# BF24.net
KiCad netlist of a schematic drawn in Altium Designer
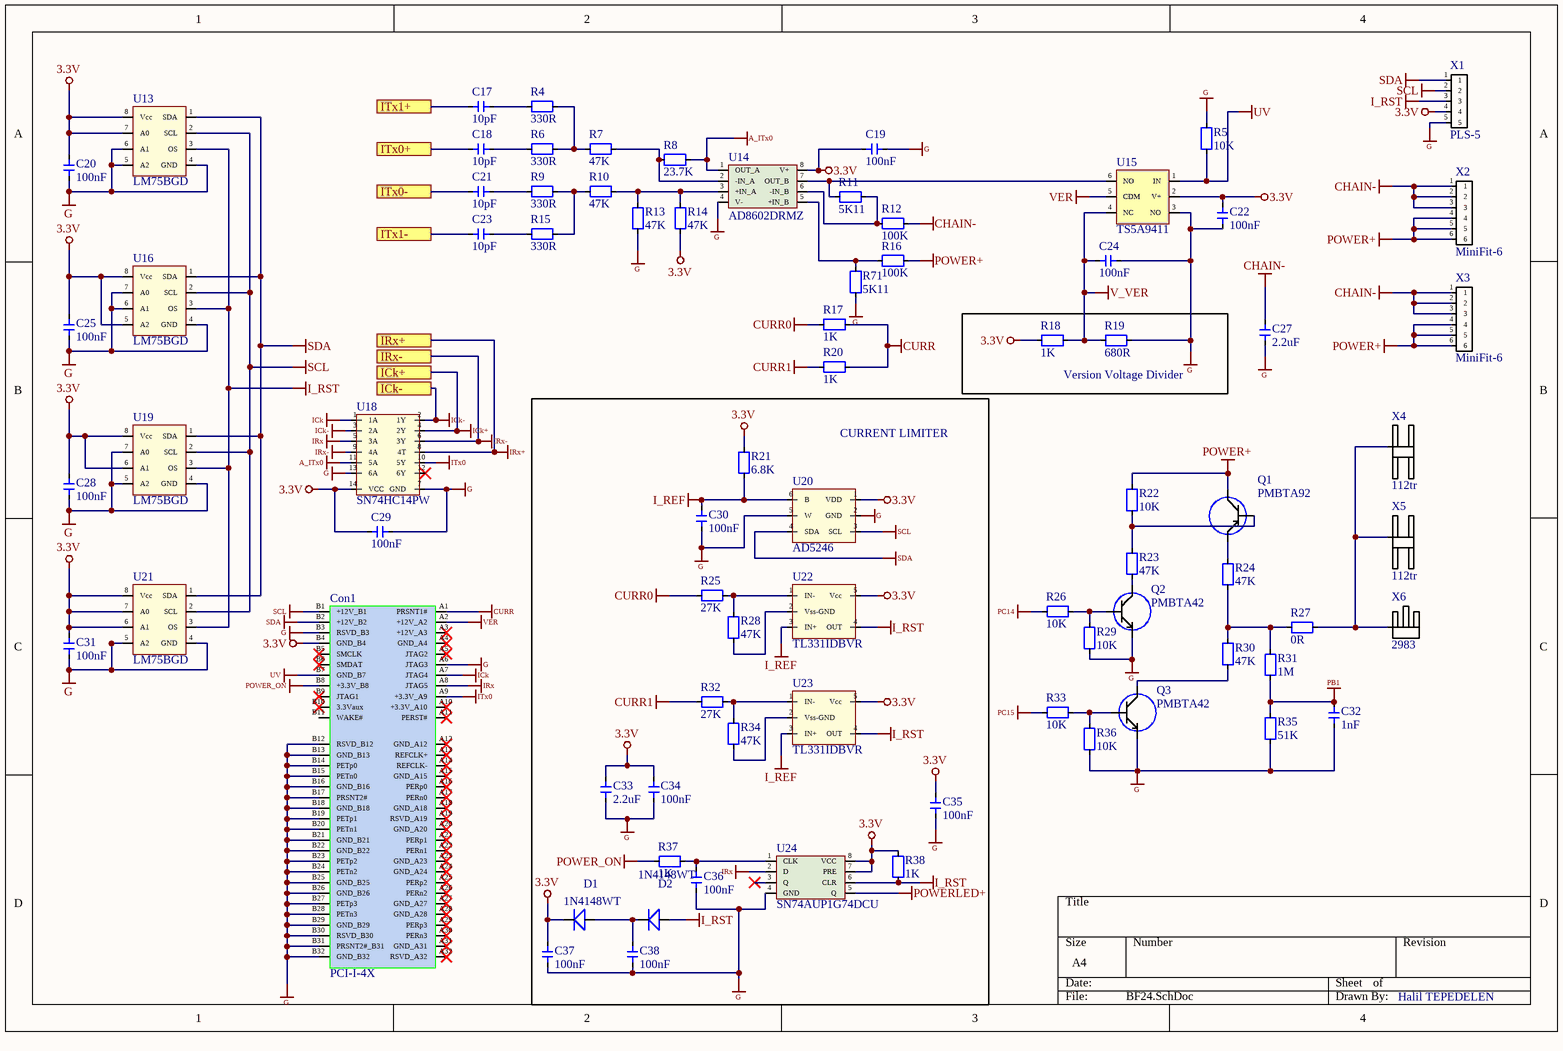
[diagram p0: BF24.SchDoc]

(export (version "E")
  (design (tool "Eeschema 10.0.6"))
  (components
    (comp (ref "C17")
      (value "10pF")
      (footprint "C-0402R")
      (libsource (lib "B9_HashBoard") (part "10pF 0402"))
    )
    (comp (ref "C18")
      (value "10pF")
      (footprint "C-0402R")
      (libsource (lib "B9_HashBoard") (part "10pF 0402"))
    )
    (comp (ref "C19")
      (value "100nF")
      (footprint "C-0402R")
      (libsource (lib "B9_HashBoard") (part "100nF 0402"))
    )
    (comp (ref "C20")
      (value "100nF")
      (footprint "C-0603W")
      (libsource (lib "B9_HashBoard") (part "100nF 0603"))
    )
    (comp (ref "C21")
      (value "10pF")
      (footprint "C-0402R")
      (libsource (lib "B9_HashBoard") (part "10pF 0402"))
    )
    (comp (ref "C22")
      (value "100nF")
      (footprint "C-0402R")
      (libsource (lib "B9_HashBoard") (part "100nF 0402"))
    )
    (comp (ref "C23")
      (value "10pF")
      (footprint "C-0402R")
      (libsource (lib "B9_HashBoard") (part "10pF 0402"))
    )
    (comp (ref "C24")
      (value "100nF")
      (footprint "C-0402R")
      (libsource (lib "B9_HashBoard") (part "100nF 0402"))
    )
    (comp (ref "C25")
      (value "100nF")
      (footprint "C-0603W")
      (libsource (lib "B9_HashBoard") (part "100nF 0603"))
    )
    (comp (ref "C27")
      (value "2.2uF")
      (footprint "R-1210R")
      (libsource (lib "B9_HashBoard") (part "2.2uF 1210"))
    )
    (comp (ref "C28")
      (value "100nF")
      (footprint "C-0603W")
      (libsource (lib "B9_HashBoard") (part "100nF 0603"))
    )
    (comp (ref "C29")
      (value "100nF")
      (footprint "C-0402R")
      (libsource (lib "B9_HashBoard") (part "100nF 0402"))
    )
    (comp (ref "C30")
      (value "100nF")
      (footprint "C-0402R")
      (libsource (lib "B9_HashBoard") (part "100nF 0402"))
    )
    (comp (ref "C31")
      (value "100nF")
      (footprint "C-0603W")
      (libsource (lib "B9_HashBoard") (part "100nF 0603"))
    )
    (comp (ref "C32") (value "1nF") (footprint "C-0603W") (libsource (lib "B9_HashBoard") (part "1nF 0603")))
    (comp (ref "C33")
      (value "2.2uF")
      (footprint "C-0402R")
      (libsource (lib "B9_HashBoard") (part "2.2uF 0402"))
    )
    (comp (ref "C34")
      (value "100nF")
      (footprint "C-0402R")
      (libsource (lib "B9_HashBoard") (part "100nF 0402"))
    )
    (comp (ref "C35")
      (value "100nF")
      (footprint "C-0402R")
      (libsource (lib "B9_HashBoard") (part "100nF 0402"))
    )
    (comp (ref "C36")
      (value "100nF")
      (footprint "C-0402R")
      (libsource (lib "B9_HashBoard") (part "100nF 0402"))
    )
    (comp (ref "C37")
      (value "100nF")
      (footprint "C-0402R")
      (libsource (lib "B9_HashBoard") (part "100nF 0402"))
    )
    (comp (ref "C38")
      (value "100nF")
      (footprint "C-0402R")
      (libsource (lib "B9_HashBoard") (part "100nF 0402"))
    )
    (comp (ref "Con1")
      (value "PCI-I-4X")
      (footprint "SAMTEC_PCIE-064-02-X-D-EMS2")
      (libsource (lib "B9_HashBoard") (part "PCI-I-4X"))
    )
    (comp (ref "D1")
      (value "1N4148WT")
      (footprint "1n4148")
      (libsource (lib "B9_HashBoard") (part "1N4148WT"))
    )
    (comp (ref "D2")
      (value "1N4148WT")
      (footprint "1n4148")
      (libsource (lib "B9_HashBoard") (part "1N4148WT"))
    )
    (comp (ref "Q1")
      (value "PMBTA92")
      (footprint "pmbta92")
      (libsource (lib "B9_HashBoard") (part "PMBTA92"))
    )
    (comp (ref "Q2")
      (value "PMBTA42")
      (footprint "pmbta42")
      (libsource (lib "B9_HashBoard") (part "PMBTA42"))
    )
    (comp (ref "Q3")
      (value "PMBTA42")
      (footprint "pmbta42")
      (libsource (lib "B9_HashBoard") (part "PMBTA42"))
    )
    (comp (ref "R4") (value "330R") (footprint "R-0402R") (libsource (lib "B9_HashBoard") (part "330R 0402")))
    (comp (ref "R5") (value "10K") (footprint "R-0402R") (libsource (lib "B9_HashBoard") (part "10K 0402")))
    (comp (ref "R6") (value "330R") (footprint "R-0402R") (libsource (lib "B9_HashBoard") (part "330R 0402")))
    (comp (ref "R7") (value "47K") (footprint "R-0402R") (libsource (lib "B9_HashBoard") (part "47K 0402")))
    (comp (ref "R8")
      (value "23.7K")
      (footprint "R-0402R")
      (libsource (lib "B9_HashBoard") (part "23.7K 0402"))
    )
    (comp (ref "R9") (value "330R") (footprint "R-0402R") (libsource (lib "B9_HashBoard") (part "330R 0402")))
    (comp (ref "R10") (value "47K") (footprint "R-0402R") (libsource (lib "B9_HashBoard") (part "47K 0402")))
    (comp (ref "R11")
      (value "5K11")
      (footprint "R-0603W")
      (libsource (lib "B9_HashBoard") (part "5K11 0603"))
    )
    (comp (ref "R12")
      (value "100K")
      (footprint "R-0603W")
      (libsource (lib "B9_HashBoard") (part "100k 0603"))
    )
    (comp (ref "R13") (value "47K") (footprint "R-0402R") (libsource (lib "B9_HashBoard") (part "47K 0402")))
    (comp (ref "R14") (value "47K") (footprint "R-0402R") (libsource (lib "B9_HashBoard") (part "47K 0402")))
    (comp (ref "R15")
      (value "330R")
      (footprint "R-0402R")
      (libsource (lib "B9_HashBoard") (part "330R 0402"))
    )
    (comp (ref "R16")
      (value "100K")
      (footprint "R-0603W")
      (libsource (lib "B9_HashBoard") (part "100k 0603"))
    )
    (comp (ref "R17") (value "1K") (footprint "R-0402R") (libsource (lib "B9_HashBoard") (part "1K 0402")))
    (comp (ref "R18") (value "1K") (footprint "R-0402R") (libsource (lib "B9_HashBoard") (part "1K 0402")))
    (comp (ref "R19")
      (value "680R")
      (footprint "R-0402R")
      (libsource (lib "B9_HashBoard") (part "680R 0402"))
    )
    (comp (ref "R20") (value "1K") (footprint "R-0402R") (libsource (lib "B9_HashBoard") (part "1K 0402")))
    (comp (ref "R21")
      (value "6.8K")
      (footprint "R-0402R")
      (libsource (lib "B9_HashBoard") (part "6.8K 0402"))
    )
    (comp (ref "R22") (value "10K") (footprint "R-0603W") (libsource (lib "B9_HashBoard") (part "10K 0603")))
    (comp (ref "R23") (value "47K") (footprint "R-1206W") (libsource (lib "B9_HashBoard") (part "47K 1206")))
    (comp (ref "R24") (value "47K") (footprint "R-1206W") (libsource (lib "B9_HashBoard") (part "47K 1206")))
    (comp (ref "R25") (value "27K") (footprint "R-0402R") (libsource (lib "B9_HashBoard") (part "27K 0402")))
    (comp (ref "R26") (value "10K") (footprint "R-0603W") (libsource (lib "B9_HashBoard") (part "10K 0603")))
    (comp (ref "R27") (value "0R") (footprint "R-0402R") (libsource (lib "B9_HashBoard") (part "0R 1206")))
    (comp (ref "R28") (value "47K") (footprint "R-0402R") (libsource (lib "B9_HashBoard") (part "47K 0402")))
    (comp (ref "R29") (value "10K") (footprint "R-0603W") (libsource (lib "B9_HashBoard") (part "10K 0603")))
    (comp (ref "R30") (value "47K") (footprint "R-1206W") (libsource (lib "B9_HashBoard") (part "47K 1206")))
    (comp (ref "R31") (value "1M") (footprint "R-0402R") (libsource (lib "B9_HashBoard") (part "1M 1206")))
    (comp (ref "R32") (value "27K") (footprint "R-0402R") (libsource (lib "B9_HashBoard") (part "27K 0402")))
    (comp (ref "R33") (value "10K") (footprint "R-0603W") (libsource (lib "B9_HashBoard") (part "10K 0603")))
    (comp (ref "R34") (value "47K") (footprint "R-0402R") (libsource (lib "B9_HashBoard") (part "47K 0402")))
    (comp (ref "R35") (value "51K") (footprint "R-0603W") (libsource (lib "B9_HashBoard") (part "51K 0603")))
    (comp (ref "R36") (value "10K") (footprint "R-0603W") (libsource (lib "B9_HashBoard") (part "10K 0603")))
    (comp (ref "R37") (value "1K") (footprint "R-0402R") (libsource (lib "B9_HashBoard") (part "1K 0402")))
    (comp (ref "R38") (value "1K") (footprint "R-0402R") (libsource (lib "B9_HashBoard") (part "1K 0402")))
    (comp (ref "R71")
      (value "5K11")
      (footprint "R-0603W")
      (libsource (lib "B9_HashBoard") (part "5K11 0603"))
    )
    (comp (ref "U13") (value "LM75BGD") (footprint "lm75") (libsource (lib "B9_HashBoard") (part "LM75BGD")))
    (comp (ref "U14")
      (value "AD8602DRMZ")
      (footprint "ad860")
      (libsource (lib "B9_HashBoard") (part "AD8602DRMZ"))
    )
    (comp (ref "U15")
      (value "TS5A9411")
      (footprint "ts5a9411")
      (libsource (lib "B9_HashBoard") (part "TS5A9411"))
    )
    (comp (ref "U16") (value "LM75BGD") (footprint "lm75") (libsource (lib "B9_HashBoard") (part "LM75BGD")))
    (comp (ref "U18")
      (value "SN74HC14PW")
      (footprint "sn74hcpw")
      (libsource (lib "B9_HashBoard") (part "SN74HC14PW"))
    )
    (comp (ref "U19") (value "LM75BGD") (footprint "lm75") (libsource (lib "B9_HashBoard") (part "LM75BGD")))
    (comp (ref "U20") (value "AD5246") (footprint "ad5246") (libsource (lib "B9_HashBoard") (part "AD5246")))
    (comp (ref "U21") (value "LM75BGD") (footprint "lm75") (libsource (lib "B9_HashBoard") (part "LM75BGD")))
    (comp (ref "U22")
      (value "TL331IDBVR")
      (footprint "tl331")
      (libsource (lib "B9_HashBoard") (part "TL331IDBVR"))
    )
    (comp (ref "U23")
      (value "TL331IDBVR")
      (footprint "tl331")
      (libsource (lib "B9_HashBoard") (part "TL331IDBVR"))
    )
    (comp (ref "U24")
      (value "SN74AUP1G74DCU")
      (footprint "sn74aup")
      (libsource (lib "B9_HashBoard") (part "SN74AUP1G74DCU"))
    )
    (comp (ref "X1") (value "PLS-5") (footprint "5pinCon") (libsource (lib "B9_HashBoard") (part "PLS-5")))
    (comp (ref "X2")
      (value "MiniFit-6")
      (footprint "MiniFit 6")
      (libsource (lib "B9_HashBoard") (part "MiniFit-6"))
    )
    (comp (ref "X3")
      (value "MiniFit-6")
      (footprint "MiniFit 6")
      (libsource (lib "B9_HashBoard") (part "MiniFit-6"))
    )
    (comp (ref "X4") (value "112tr") (footprint "112tr") (libsource (lib "B9_HashBoard") (part "112tr")))
    (comp (ref "X5") (value "112tr") (footprint "112tr") (libsource (lib "B9_HashBoard") (part "112tr")))
    (comp (ref "X6") (value "2983") (footprint "2983") (libsource (lib "B9_HashBoard") (part "2983")))
  )
  (nets
    (net (code "1") (name "/ITx0+") (class "Default")
      (node (ref "C18") (pin "1") (pinfunction "1_1") (pintype "passive"))
    )
    (net (code "2") (name "/ITx0-") (class "Default")
      (node (ref "C21") (pin "1") (pinfunction "1_1") (pintype "passive"))
    )
    (net (code "3") (name "/ITx1+") (class "Default")
      (node (ref "C17") (pin "1") (pinfunction "1_1") (pintype "passive"))
    )
    (net (code "4") (name "/ITx1-") (class "Default")
      (node (ref "C23") (pin "1") (pinfunction "1_1") (pintype "passive"))
    )
    (net (code "5") (name "3.3V") (class "Default")
      (node (ref "C19") (pin "1") (pinfunction "1_1") (pintype "passive"))
      (node (ref "C20") (pin "2") (pinfunction "2_2") (pintype "passive"))
      (node (ref "C22") (pin "2") (pinfunction "2_2") (pintype "passive"))
      (node (ref "C25") (pin "2") (pinfunction "2_2") (pintype "passive"))
      (node (ref "C28") (pin "2") (pinfunction "2_2") (pintype "passive"))
      (node (ref "C29") (pin "1") (pinfunction "1_1") (pintype "passive"))
      (node (ref "C31") (pin "2") (pinfunction "2_2") (pintype "passive"))
      (node (ref "C33") (pin "2") (pinfunction "2_2") (pintype "passive"))
      (node (ref "C34") (pin "2") (pinfunction "2_2") (pintype "passive"))
      (node (ref "C35") (pin "2") (pinfunction "2_2") (pintype "passive"))
      (node (ref "C37") (pin "2") (pinfunction "2_2") (pintype "passive"))
      (node (ref "Con1") (pin "B4") (pinfunction "GND_B4_B4") (pintype "passive"))
      (node (ref "D1") (pin "1") (pinfunction "1_1") (pintype "passive"))
      (node (ref "R14") (pin "1") (pinfunction "1_1") (pintype "passive"))
      (node (ref "R18") (pin "1") (pinfunction "1_1") (pintype "passive"))
      (node (ref "R21") (pin "2") (pinfunction "2_2") (pintype "passive"))
      (node (ref "R38") (pin "2") (pinfunction "2_2") (pintype "passive"))
      (node (ref "U13") (pin "7") (pinfunction "A0_7") (pintype "passive"))
      (node (ref "U13") (pin "8") (pinfunction "Vcc_8") (pintype "passive"))
      (node (ref "U14") (pin "8") (pinfunction "V+_8") (pintype "passive"))
      (node (ref "U15") (pin "2") (pinfunction "V+_2") (pintype "passive"))
      (node (ref "U16") (pin "5") (pinfunction "A2_5") (pintype "passive"))
      (node (ref "U16") (pin "8") (pinfunction "Vcc_8") (pintype "passive"))
      (node (ref "U18") (pin "14") (pinfunction "VCC_14") (pintype "passive"))
      (node (ref "U19") (pin "6") (pinfunction "A1_6") (pintype "passive"))
      (node (ref "U19") (pin "8") (pinfunction "Vcc_8") (pintype "passive"))
      (node (ref "U20") (pin "1") (pinfunction "VDD_1") (pintype "passive"))
      (node (ref "U21") (pin "6") (pinfunction "A1_6") (pintype "passive"))
      (node (ref "U21") (pin "7") (pinfunction "A0_7") (pintype "passive"))
      (node (ref "U21") (pin "8") (pinfunction "Vcc_8") (pintype "passive"))
      (node (ref "U22") (pin "5") (pinfunction "Vcc_5") (pintype "passive"))
      (node (ref "U23") (pin "5") (pinfunction "Vcc_5") (pintype "passive"))
      (node (ref "U24") (pin "7") (pinfunction "PRE_7") (pintype "passive"))
      (node (ref "U24") (pin "8") (pinfunction "VCC_8") (pintype "passive"))
      (node (ref "X1") (pin "4") (pinfunction "4_4") (pintype "passive"))
    )
    (net (code "6") (name "A_ITx0") (class "Default")
      (node (ref "R8") (pin "2") (pinfunction "2_2") (pintype "passive"))
      (node (ref "U14") (pin "1") (pinfunction "OUT_A_1") (pintype "passive"))
      (node (ref "U18") (pin "11") (pinfunction "5A_11") (pintype "passive"))
    )
    (net (code "7") (name "CHAIN-") (class "Default")
      (node (ref "C27") (pin "2") (pinfunction "2_2") (pintype "passive"))
      (node (ref "R12") (pin "2") (pinfunction "2_2") (pintype "passive"))
      (node (ref "X2") (pin "1") (pinfunction "1_1") (pintype "passive"))
      (node (ref "X2") (pin "2") (pinfunction "2_2") (pintype "passive"))
      (node (ref "X2") (pin "3") (pinfunction "3_3") (pintype "passive"))
      (node (ref "X3") (pin "1") (pinfunction "1_1") (pintype "passive"))
      (node (ref "X3") (pin "2") (pinfunction "2_2") (pintype "passive"))
      (node (ref "X3") (pin "3") (pinfunction "3_3") (pintype "passive"))
    )
    (net (code "8") (name "CURR") (class "Default")
      (node (ref "Con1") (pin "A1") (pinfunction "PRSNT1#_A1") (pintype "passive"))
      (node (ref "R17") (pin "2") (pinfunction "2_2") (pintype "passive"))
      (node (ref "R20") (pin "2") (pinfunction "2_2") (pintype "passive"))
    )
    (net (code "9") (name "CURR0") (class "Default")
      (node (ref "R17") (pin "1") (pinfunction "1_1") (pintype "passive"))
      (node (ref "R25") (pin "1") (pinfunction "1_1") (pintype "passive"))
    )
    (net (code "10") (name "CURR1") (class "Default")
      (node (ref "R20") (pin "1") (pinfunction "1_1") (pintype "passive"))
      (node (ref "R32") (pin "1") (pinfunction "1_1") (pintype "passive"))
    )
    (net (code "11") (name "G") (class "Default")
      (node (ref "C19") (pin "2") (pinfunction "2_2") (pintype "passive"))
      (node (ref "C20") (pin "1") (pinfunction "1_1") (pintype "passive"))
      (node (ref "C22") (pin "1") (pinfunction "1_1") (pintype "passive"))
      (node (ref "C24") (pin "2") (pinfunction "2_2") (pintype "passive"))
      (node (ref "C25") (pin "1") (pinfunction "1_1") (pintype "passive"))
      (node (ref "C27") (pin "1") (pinfunction "1_1") (pintype "passive"))
      (node (ref "C28") (pin "1") (pinfunction "1_1") (pintype "passive"))
      (node (ref "C29") (pin "2") (pinfunction "2_2") (pintype "passive"))
      (node (ref "C30") (pin "1") (pinfunction "1_1") (pintype "passive"))
      (node (ref "C31") (pin "1") (pinfunction "1_1") (pintype "passive"))
      (node (ref "C32") (pin "1") (pinfunction "1_1") (pintype "passive"))
      (node (ref "C33") (pin "1") (pinfunction "1_1") (pintype "passive"))
      (node (ref "C34") (pin "1") (pinfunction "1_1") (pintype "passive"))
      (node (ref "C35") (pin "1") (pinfunction "1_1") (pintype "passive"))
      (node (ref "C36") (pin "1") (pinfunction "1_1") (pintype "passive"))
      (node (ref "C37") (pin "1") (pinfunction "1_1") (pintype "passive"))
      (node (ref "C38") (pin "1") (pinfunction "1_1") (pintype "passive"))
      (node (ref "Con1") (pin "A6") (pinfunction "JTAG3_A6") (pintype "passive"))
      (node (ref "Con1") (pin "B12") (pinfunction "RSVD_B12_B12") (pintype "passive"))
      (node (ref "Con1") (pin "B13") (pinfunction "GND_B13_B13") (pintype "passive"))
      (node (ref "Con1") (pin "B14") (pinfunction "PETp0_B14") (pintype "passive"))
      (node (ref "Con1") (pin "B15") (pinfunction "PETn0_B15") (pintype "passive"))
      (node (ref "Con1") (pin "B16") (pinfunction "GND_B16_B16") (pintype "passive"))
      (node (ref "Con1") (pin "B17") (pinfunction "PRSNT2#_B17") (pintype "passive"))
      (node (ref "Con1") (pin "B18") (pinfunction "GND_B18_B18") (pintype "passive"))
      (node (ref "Con1") (pin "B19") (pinfunction "PETp1_B19") (pintype "passive"))
      (node (ref "Con1") (pin "B20") (pinfunction "PETn1_B20") (pintype "passive"))
      (node (ref "Con1") (pin "B21") (pinfunction "GND_B21_B21") (pintype "passive"))
      (node (ref "Con1") (pin "B22") (pinfunction "GND_B22_B22") (pintype "passive"))
      (node (ref "Con1") (pin "B23") (pinfunction "PETp2_B23") (pintype "passive"))
      (node (ref "Con1") (pin "B24") (pinfunction "PETn2_B24") (pintype "passive"))
      (node (ref "Con1") (pin "B25") (pinfunction "GND_B25_B25") (pintype "passive"))
      (node (ref "Con1") (pin "B26") (pinfunction "GND_B26_B26") (pintype "passive"))
      (node (ref "Con1") (pin "B27") (pinfunction "PETp3_B27") (pintype "passive"))
      (node (ref "Con1") (pin "B28") (pinfunction "PETn3_B28") (pintype "passive"))
      (node (ref "Con1") (pin "B29") (pinfunction "GND_B29_B29") (pintype "passive"))
      (node (ref "Con1") (pin "B3") (pinfunction "RSVD_B3_B3") (pintype "passive"))
      (node (ref "Con1") (pin "B30") (pinfunction "RSVD_B30_B30") (pintype "passive"))
      (node (ref "Con1") (pin "B31") (pinfunction "PRSNT2#_B31_B31") (pintype "passive"))
      (node (ref "Con1") (pin "B32") (pinfunction "GND_B32_B32") (pintype "passive"))
      (node (ref "Q2") (pin "2") (pinfunction "2_2") (pintype "passive"))
      (node (ref "Q3") (pin "2") (pinfunction "2_2") (pintype "passive"))
      (node (ref "R13") (pin "1") (pinfunction "1_1") (pintype "passive"))
      (node (ref "R19") (pin "2") (pinfunction "2_2") (pintype "passive"))
      (node (ref "R29") (pin "1") (pinfunction "1_1") (pintype "passive"))
      (node (ref "R35") (pin "1") (pinfunction "1_1") (pintype "passive"))
      (node (ref "R36") (pin "1") (pinfunction "1_1") (pintype "passive"))
      (node (ref "R5") (pin "2") (pinfunction "2_2") (pintype "passive"))
      (node (ref "R71") (pin "1") (pinfunction "1_1") (pintype "passive"))
      (node (ref "U13") (pin "4") (pinfunction "GND_4") (pintype "passive"))
      (node (ref "U13") (pin "5") (pinfunction "A2_5") (pintype "passive"))
      (node (ref "U13") (pin "6") (pinfunction "A1_6") (pintype "passive"))
      (node (ref "U14") (pin "4") (pinfunction "V-_4") (pintype "passive"))
      (node (ref "U15") (pin "3") (pinfunction "NO_3") (pintype "passive"))
      (node (ref "U16") (pin "4") (pinfunction "GND_4") (pintype "passive"))
      (node (ref "U16") (pin "6") (pinfunction "A1_6") (pintype "passive"))
      (node (ref "U16") (pin "7") (pinfunction "A0_7") (pintype "passive"))
      (node (ref "U18") (pin "13") (pinfunction "6A_13") (pintype "passive"))
      (node (ref "U18") (pin "7") (pinfunction "GND_7") (pintype "passive"))
      (node (ref "U19") (pin "4") (pinfunction "GND_4") (pintype "passive"))
      (node (ref "U19") (pin "5") (pinfunction "A2_5") (pintype "passive"))
      (node (ref "U19") (pin "7") (pinfunction "A0_7") (pintype "passive"))
      (node (ref "U20") (pin "2") (pinfunction "GND_2") (pintype "passive"))
      (node (ref "U20") (pin "5") (pinfunction "W_5") (pintype "passive"))
      (node (ref "U21") (pin "4") (pinfunction "GND_4") (pintype "passive"))
      (node (ref "U21") (pin "5") (pinfunction "A2_5") (pintype "passive"))
      (node (ref "U24") (pin "4") (pinfunction "GND_4") (pintype "passive"))
      (node (ref "X1") (pin "5") (pinfunction "5_5") (pintype "passive"))
    )
    (net (code "12") (name "ICk") (class "Default")
      (node (ref "Con1") (pin "A7") (pinfunction "JTAG4_A7") (pintype "passive"))
      (node (ref "U18") (pin "1") (pinfunction "1A_1") (pintype "passive"))
    )
    (net (code "13") (name "ICk+") (class "Default")
      (node (ref "U18") (pin "4") (pinfunction "2Y_4") (pintype "passive"))
    )
    (net (code "14") (name "ICk-") (class "Default")
      (node (ref "U18") (pin "2") (pinfunction "1Y_2") (pintype "passive"))
      (node (ref "U18") (pin "3") (pinfunction "2A_3") (pintype "passive"))
    )
    (net (code "15") (name "IRx") (class "Default")
      (node (ref "Con1") (pin "A8") (pinfunction "JTAG5_A8") (pintype "passive"))
      (node (ref "U18") (pin "5") (pinfunction "3A_5") (pintype "passive"))
      (node (ref "U24") (pin "2") (pinfunction "D_2") (pintype "passive"))
    )
    (net (code "16") (name "IRx+") (class "Default")
      (node (ref "U18") (pin "8") (pinfunction "4T_8") (pintype "passive"))
    )
    (net (code "17") (name "IRx-") (class "Default")
      (node (ref "U18") (pin "6") (pinfunction "3Y_6") (pintype "passive"))
      (node (ref "U18") (pin "9") (pinfunction "4A_9") (pintype "passive"))
    )
    (net (code "18") (name "ITx0") (class "Default")
      (node (ref "Con1") (pin "A9") (pinfunction "+3.3V_A9_A9") (pintype "passive"))
      (node (ref "U18") (pin "10") (pinfunction "5Y_10") (pintype "passive"))
    )
    (net (code "19") (name "I_REF") (class "Default")
      (node (ref "C30") (pin "2") (pinfunction "2_2") (pintype "passive"))
      (node (ref "R21") (pin "1") (pinfunction "1_1") (pintype "passive"))
      (node (ref "U20") (pin "6") (pinfunction "B_6") (pintype "passive"))
      (node (ref "U22") (pin "3") (pinfunction "IN+_3") (pintype "passive"))
      (node (ref "U23") (pin "3") (pinfunction "IN+_3") (pintype "passive"))
    )
    (net (code "20") (name "I_RST") (class "Default")
      (node (ref "D2") (pin "2") (pinfunction "2_2") (pintype "passive"))
      (node (ref "R38") (pin "1") (pinfunction "1_1") (pintype "passive"))
      (node (ref "U13") (pin "3") (pinfunction "OS_3") (pintype "passive"))
      (node (ref "U16") (pin "3") (pinfunction "OS_3") (pintype "passive"))
      (node (ref "U19") (pin "3") (pinfunction "OS_3") (pintype "passive"))
      (node (ref "U21") (pin "3") (pinfunction "OS_3") (pintype "passive"))
      (node (ref "U22") (pin "4") (pinfunction "OUT_4") (pintype "passive"))
      (node (ref "U23") (pin "4") (pinfunction "OUT_4") (pintype "passive"))
      (node (ref "U24") (pin "6") (pinfunction "CLR_6") (pintype "passive"))
      (node (ref "X1") (pin "3") (pinfunction "3_3") (pintype "passive"))
    )
    (net (code "21") (name "Net-(C17-Pad2)") (class "Default")
      (node (ref "C17") (pin "2") (pinfunction "2_2") (pintype "passive"))
      (node (ref "R4") (pin "1") (pinfunction "1_1") (pintype "passive"))
    )
    (net (code "22") (name "Net-(C18-Pad2)") (class "Default")
      (node (ref "C18") (pin "2") (pinfunction "2_2") (pintype "passive"))
      (node (ref "R6") (pin "1") (pinfunction "1_1") (pintype "passive"))
    )
    (net (code "23") (name "Net-(C21-Pad2)") (class "Default")
      (node (ref "C21") (pin "2") (pinfunction "2_2") (pintype "passive"))
      (node (ref "R9") (pin "1") (pinfunction "1_1") (pintype "passive"))
    )
    (net (code "24") (name "Net-(C23-Pad2)") (class "Default")
      (node (ref "C23") (pin "2") (pinfunction "2_2") (pintype "passive"))
      (node (ref "R15") (pin "1") (pinfunction "1_1") (pintype "passive"))
    )
    (net (code "25") (name "Net-(C38-Pad2)") (class "Default")
      (node (ref "C38") (pin "2") (pinfunction "2_2") (pintype "passive"))
      (node (ref "D1") (pin "2") (pinfunction "2_2") (pintype "passive"))
      (node (ref "D2") (pin "1") (pinfunction "1_1") (pintype "passive"))
    )
    (net (code "26") (name "Net-(Q1-Pad1)") (class "Default")
      (node (ref "Q1") (pin "1") (pinfunction "1_1") (pintype "passive"))
      (node (ref "R22") (pin "1") (pinfunction "1_1") (pintype "passive"))
      (node (ref "R23") (pin "2") (pinfunction "2_2") (pintype "passive"))
    )
    (net (code "27") (name "Net-(Q1-Pad3)") (class "Default")
      (node (ref "Q1") (pin "3") (pinfunction "3_3") (pintype "passive"))
      (node (ref "R24") (pin "2") (pinfunction "2_2") (pintype "passive"))
    )
    (net (code "28") (name "Net-(Q2-Pad1)") (class "Default")
      (node (ref "Q2") (pin "1") (pinfunction "1_1") (pintype "passive"))
      (node (ref "R26") (pin "2") (pinfunction "2_2") (pintype "passive"))
      (node (ref "R29") (pin "2") (pinfunction "2_2") (pintype "passive"))
    )
    (net (code "29") (name "Net-(Q2-Pad3)") (class "Default")
      (node (ref "Q2") (pin "3") (pinfunction "3_3") (pintype "passive"))
      (node (ref "R23") (pin "1") (pinfunction "1_1") (pintype "passive"))
    )
    (net (code "30") (name "Net-(Q3-Pad1)") (class "Default")
      (node (ref "Q3") (pin "1") (pinfunction "1_1") (pintype "passive"))
      (node (ref "R33") (pin "2") (pinfunction "2_2") (pintype "passive"))
      (node (ref "R36") (pin "2") (pinfunction "2_2") (pintype "passive"))
    )
    (net (code "31") (name "Net-(Q3-Pad3)") (class "Default")
      (node (ref "Q3") (pin "3") (pinfunction "3_3") (pintype "passive"))
      (node (ref "R30") (pin "1") (pinfunction "1_1") (pintype "passive"))
    )
    (net (code "32") (name "Net-(R4-Pad2)") (class "Default")
      (node (ref "R4") (pin "2") (pinfunction "2_2") (pintype "passive"))
      (node (ref "R6") (pin "2") (pinfunction "2_2") (pintype "passive"))
      (node (ref "R7") (pin "1") (pinfunction "1_1") (pintype "passive"))
    )
    (net (code "33") (name "Net-(R10-Pad1)") (class "Default")
      (node (ref "R10") (pin "1") (pinfunction "1_1") (pintype "passive"))
      (node (ref "R15") (pin "2") (pinfunction "2_2") (pintype "passive"))
      (node (ref "R9") (pin "2") (pinfunction "2_2") (pintype "passive"))
    )
    (net (code "34") (name "Net-(R24-Pad1)") (class "Default")
      (node (ref "R24") (pin "1") (pinfunction "1_1") (pintype "passive"))
      (node (ref "R27") (pin "1") (pinfunction "1_1") (pintype "passive"))
      (node (ref "R30") (pin "2") (pinfunction "2_2") (pintype "passive"))
      (node (ref "R31") (pin "2") (pinfunction "2_2") (pintype "passive"))
    )
    (net (code "35") (name "Net-(R27-Pad2)") (class "Default")
      (node (ref "R27") (pin "2") (pinfunction "2_2") (pintype "passive"))
      (node (ref "X4") (pin "1") (pinfunction "1_1") (pintype "passive"))
      (node (ref "X5") (pin "1") (pinfunction "1_1") (pintype "passive"))
      (node (ref "X6") (pin "1") (pinfunction "1_1") (pintype "passive"))
    )
    (net (code "36") (name "Net-(U14-+IN_A)") (class "Default")
      (node (ref "R10") (pin "2") (pinfunction "2_2") (pintype "passive"))
      (node (ref "R13") (pin "2") (pinfunction "2_2") (pintype "passive"))
      (node (ref "R14") (pin "2") (pinfunction "2_2") (pintype "passive"))
      (node (ref "U14") (pin "3") (pinfunction "+IN_A_3") (pintype "passive"))
    )
    (net (code "37") (name "Net-(U14-+IN_B)") (class "Default")
      (node (ref "R16") (pin "1") (pinfunction "1_1") (pintype "passive"))
      (node (ref "R71") (pin "2") (pinfunction "2_2") (pintype "passive"))
      (node (ref "U14") (pin "5") (pinfunction "+IN_B_5") (pintype "passive"))
    )
    (net (code "38") (name "Net-(U14--IN_A)") (class "Default")
      (node (ref "R7") (pin "2") (pinfunction "2_2") (pintype "passive"))
      (node (ref "R8") (pin "1") (pinfunction "1_1") (pintype "passive"))
      (node (ref "U14") (pin "2") (pinfunction "-IN_A_2") (pintype "passive"))
    )
    (net (code "39") (name "Net-(U14--IN_B)") (class "Default")
      (node (ref "R11") (pin "2") (pinfunction "2_2") (pintype "passive"))
      (node (ref "R12") (pin "1") (pinfunction "1_1") (pintype "passive"))
      (node (ref "U14") (pin "6") (pinfunction "-IN_B_6") (pintype "passive"))
    )
    (net (code "40") (name "Net-(U14-OUT_B)") (class "Default")
      (node (ref "R11") (pin "1") (pinfunction "1_1") (pintype "passive"))
      (node (ref "U14") (pin "7") (pinfunction "OUT_B_7") (pintype "passive"))
      (node (ref "U15") (pin "6") (pinfunction "NO_6") (pintype "passive"))
    )
    (net (code "41") (name "Net-(U22-IN-)") (class "Default")
      (node (ref "R25") (pin "2") (pinfunction "2_2") (pintype "passive"))
      (node (ref "R28") (pin "2") (pinfunction "2_2") (pintype "passive"))
      (node (ref "U22") (pin "1") (pinfunction "IN-_1") (pintype "passive"))
    )
    (net (code "42") (name "Net-(U22-Vss-GND)") (class "Default")
      (node (ref "R28") (pin "1") (pinfunction "1_1") (pintype "passive"))
      (node (ref "U22") (pin "2") (pinfunction "Vss-GND_2") (pintype "passive"))
    )
    (net (code "43") (name "Net-(U23-IN-)") (class "Default")
      (node (ref "R32") (pin "2") (pinfunction "2_2") (pintype "passive"))
      (node (ref "R34") (pin "2") (pinfunction "2_2") (pintype "passive"))
      (node (ref "U23") (pin "1") (pinfunction "IN-_1") (pintype "passive"))
    )
    (net (code "44") (name "Net-(U23-Vss-GND)") (class "Default")
      (node (ref "R34") (pin "1") (pinfunction "1_1") (pintype "passive"))
      (node (ref "U23") (pin "2") (pinfunction "Vss-GND_2") (pintype "passive"))
    )
    (net (code "45") (name "Net-(U24-CLK)") (class "Default")
      (node (ref "C36") (pin "2") (pinfunction "2_2") (pintype "passive"))
      (node (ref "R37") (pin "2") (pinfunction "2_2") (pintype "passive"))
      (node (ref "U24") (pin "1") (pinfunction "CLK_1") (pintype "passive"))
    )
    (net (code "46") (name "PB1") (class "Default")
      (node (ref "C32") (pin "2") (pinfunction "2_2") (pintype "passive"))
      (node (ref "R31") (pin "1") (pinfunction "1_1") (pintype "passive"))
      (node (ref "R35") (pin "2") (pinfunction "2_2") (pintype "passive"))
    )
    (net (code "47") (name "PC14") (class "Default")
      (node (ref "R26") (pin "1") (pinfunction "1_1") (pintype "passive"))
    )
    (net (code "48") (name "PC15") (class "Default")
      (node (ref "R33") (pin "1") (pinfunction "1_1") (pintype "passive"))
    )
    (net (code "49") (name "POWER+") (class "Default")
      (node (ref "Q1") (pin "2") (pinfunction "2_2") (pintype "passive"))
      (node (ref "R16") (pin "2") (pinfunction "2_2") (pintype "passive"))
      (node (ref "R22") (pin "2") (pinfunction "2_2") (pintype "passive"))
      (node (ref "X2") (pin "4") (pinfunction "4_4") (pintype "passive"))
      (node (ref "X2") (pin "5") (pinfunction "5_5") (pintype "passive"))
      (node (ref "X2") (pin "6") (pinfunction "6_6") (pintype "passive"))
      (node (ref "X3") (pin "4") (pinfunction "4_4") (pintype "passive"))
      (node (ref "X3") (pin "5") (pinfunction "5_5") (pintype "passive"))
      (node (ref "X3") (pin "6") (pinfunction "6_6") (pintype "passive"))
    )
    (net (code "50") (name "POWERLED+") (class "Default")
      (node (ref "U24") (pin "5") (pinfunction "Q_5") (pintype "passive"))
    )
    (net (code "51") (name "POWER_ON") (class "Default")
      (node (ref "Con1") (pin "B8") (pinfunction "+3.3V_B8_B8") (pintype "passive"))
      (node (ref "R37") (pin "1") (pinfunction "1_1") (pintype "passive"))
    )
    (net (code "52") (name "SCL") (class "Default")
      (node (ref "Con1") (pin "B1") (pinfunction "+12V_B1_B1") (pintype "passive"))
      (node (ref "U13") (pin "2") (pinfunction "SCL_2") (pintype "passive"))
      (node (ref "U16") (pin "2") (pinfunction "SCL_2") (pintype "passive"))
      (node (ref "U19") (pin "2") (pinfunction "SCL_2") (pintype "passive"))
      (node (ref "U20") (pin "3") (pinfunction "SCL_3") (pintype "passive"))
      (node (ref "U21") (pin "2") (pinfunction "SCL_2") (pintype "passive"))
      (node (ref "X1") (pin "2") (pinfunction "2_2") (pintype "passive"))
    )
    (net (code "53") (name "SDA") (class "Default")
      (node (ref "Con1") (pin "B2") (pinfunction "+12V_B2_B2") (pintype "passive"))
      (node (ref "U13") (pin "1") (pinfunction "SDA_1") (pintype "passive"))
      (node (ref "U16") (pin "1") (pinfunction "SDA_1") (pintype "passive"))
      (node (ref "U19") (pin "1") (pinfunction "SDA_1") (pintype "passive"))
      (node (ref "U20") (pin "4") (pinfunction "SDA_4") (pintype "passive"))
      (node (ref "U21") (pin "1") (pinfunction "SDA_1") (pintype "passive"))
      (node (ref "X1") (pin "1") (pinfunction "1_1") (pintype "passive"))
    )
    (net (code "54") (name "UV") (class "Default")
      (node (ref "Con1") (pin "B7") (pinfunction "GND_B7_B7") (pintype "passive"))
      (node (ref "R5") (pin "1") (pinfunction "1_1") (pintype "passive"))
      (node (ref "U15") (pin "1") (pinfunction "IN_1") (pintype "passive"))
    )
    (net (code "55") (name "VER") (class "Default")
      (node (ref "Con1") (pin "A2") (pinfunction "+12V_A2_A2") (pintype "passive"))
      (node (ref "U15") (pin "5") (pinfunction "CDM_5") (pintype "passive"))
    )
    (net (code "56") (name "V_VER") (class "Default")
      (node (ref "C24") (pin "1") (pinfunction "1_1") (pintype "passive"))
      (node (ref "R18") (pin "2") (pinfunction "2_2") (pintype "passive"))
      (node (ref "R19") (pin "1") (pinfunction "1_1") (pintype "passive"))
      (node (ref "U15") (pin "4") (pinfunction "NC_4") (pintype "passive"))
    )
    (net (code "57") (name "unconnected-(Con1-+3.3V_A10-PadA10)") (class "Default")
      (node (ref "Con1") (pin "A10") (pinfunction "+3.3V_A10_A10") (pintype "passive+no_connect"))
    )
    (net (code "58") (name "unconnected-(Con1-+12V_A3-PadA3)") (class "Default")
      (node (ref "Con1") (pin "A3") (pinfunction "+12V_A3_A3") (pintype "passive+no_connect"))
    )
    (net (code "59") (name "unconnected-(Con1-3.3Vaux-PadB10)") (class "Default")
      (node (ref "Con1") (pin "B10") (pinfunction "3.3Vaux_B10") (pintype "passive+no_connect"))
    )
    (net (code "60") (name "unconnected-(Con1-GND_A4-PadA4)") (class "Default")
      (node (ref "Con1") (pin "A4") (pinfunction "GND_A4_A4") (pintype "passive+no_connect"))
    )
    (net (code "61") (name "unconnected-(Con1-GND_A12-PadA12)") (class "Default")
      (node (ref "Con1") (pin "A12") (pinfunction "GND_A12_A12") (pintype "passive+no_connect"))
    )
    (net (code "62") (name "unconnected-(Con1-GND_A15-PadA15)") (class "Default")
      (node (ref "Con1") (pin "A15") (pinfunction "GND_A15_A15") (pintype "passive+no_connect"))
    )
    (net (code "63") (name "unconnected-(Con1-GND_A18-PadA18)") (class "Default")
      (node (ref "Con1") (pin "A18") (pinfunction "GND_A18_A18") (pintype "passive+no_connect"))
    )
    (net (code "64") (name "unconnected-(Con1-GND_A20-PadA20)") (class "Default")
      (node (ref "Con1") (pin "A20") (pinfunction "GND_A20_A20") (pintype "passive+no_connect"))
    )
    (net (code "65") (name "unconnected-(Con1-GND_A23-PadA23)") (class "Default")
      (node (ref "Con1") (pin "A23") (pinfunction "GND_A23_A23") (pintype "passive+no_connect"))
    )
    (net (code "66") (name "unconnected-(Con1-GND_A24-PadA24)") (class "Default")
      (node (ref "Con1") (pin "A24") (pinfunction "GND_A24_A24") (pintype "passive+no_connect"))
    )
    (net (code "67") (name "unconnected-(Con1-GND_A27-PadA27)") (class "Default")
      (node (ref "Con1") (pin "A27") (pinfunction "GND_A27_A27") (pintype "passive+no_connect"))
    )
    (net (code "68") (name "unconnected-(Con1-GND_A28-PadA28)") (class "Default")
      (node (ref "Con1") (pin "A28") (pinfunction "GND_A28_A28") (pintype "passive+no_connect"))
    )
    (net (code "69") (name "unconnected-(Con1-GND_A31-PadA31)") (class "Default")
      (node (ref "Con1") (pin "A31") (pinfunction "GND_A31_A31") (pintype "passive+no_connect"))
    )
    (net (code "70") (name "unconnected-(Con1-JTAG1-PadB9)") (class "Default")
      (node (ref "Con1") (pin "B9") (pinfunction "JTAG1_B9") (pintype "passive+no_connect"))
    )
    (net (code "71") (name "unconnected-(Con1-JTAG2-PadA5)") (class "Default")
      (node (ref "Con1") (pin "A5") (pinfunction "JTAG2_A5") (pintype "passive+no_connect"))
    )
    (net (code "72") (name "unconnected-(Con1-PERST#-PadA11)") (class "Default")
      (node (ref "Con1") (pin "A11") (pinfunction "PERST#_A11") (pintype "passive+no_connect"))
    )
    (net (code "73") (name "unconnected-(Con1-PERn0-PadA17)") (class "Default")
      (node (ref "Con1") (pin "A17") (pinfunction "PERn0_A17") (pintype "passive+no_connect"))
    )
    (net (code "74") (name "unconnected-(Con1-PERn1-PadA22)") (class "Default")
      (node (ref "Con1") (pin "A22") (pinfunction "PERn1_A22") (pintype "passive+no_connect"))
    )
    (net (code "75") (name "unconnected-(Con1-PERn2-PadA26)") (class "Default")
      (node (ref "Con1") (pin "A26") (pinfunction "PERn2_A26") (pintype "passive+no_connect"))
    )
    (net (code "76") (name "unconnected-(Con1-PERn3-PadA30)") (class "Default")
      (node (ref "Con1") (pin "A30") (pinfunction "PERn3_A30") (pintype "passive+no_connect"))
    )
    (net (code "77") (name "unconnected-(Con1-PERp0-PadA16)") (class "Default")
      (node (ref "Con1") (pin "A16") (pinfunction "PERp0_A16") (pintype "passive+no_connect"))
    )
    (net (code "78") (name "unconnected-(Con1-PERp1-PadA21)") (class "Default")
      (node (ref "Con1") (pin "A21") (pinfunction "PERp1_A21") (pintype "passive+no_connect"))
    )
    (net (code "79") (name "unconnected-(Con1-PERp2-PadA25)") (class "Default")
      (node (ref "Con1") (pin "A25") (pinfunction "PERp2_A25") (pintype "passive+no_connect"))
    )
    (net (code "80") (name "unconnected-(Con1-PERp3-PadA29)") (class "Default")
      (node (ref "Con1") (pin "A29") (pinfunction "PERp3_A29") (pintype "passive+no_connect"))
    )
    (net (code "81") (name "unconnected-(Con1-REFCLK+-PadA13)") (class "Default")
      (node (ref "Con1") (pin "A13") (pinfunction "REFCLK+_A13") (pintype "passive+no_connect"))
    )
    (net (code "82") (name "unconnected-(Con1-REFCLK--PadA14)") (class "Default")
      (node (ref "Con1") (pin "A14") (pinfunction "REFCLK-_A14") (pintype "passive+no_connect"))
    )
    (net (code "83") (name "unconnected-(Con1-RSVD_A19-PadA19)") (class "Default")
      (node (ref "Con1") (pin "A19") (pinfunction "RSVD_A19_A19") (pintype "passive+no_connect"))
    )
    (net (code "84") (name "unconnected-(Con1-RSVD_A32-PadA32)") (class "Default")
      (node (ref "Con1") (pin "A32") (pinfunction "RSVD_A32_A32") (pintype "passive+no_connect"))
    )
    (net (code "85") (name "unconnected-(Con1-SMCLK-PadB5)") (class "Default")
      (node (ref "Con1") (pin "B5") (pinfunction "SMCLK_B5") (pintype "passive+no_connect"))
    )
    (net (code "86") (name "unconnected-(Con1-SMDAT-PadB6)") (class "Default")
      (node (ref "Con1") (pin "B6") (pinfunction "SMDAT_B6") (pintype "passive+no_connect"))
    )
    (net (code "87") (name "unconnected-(Con1-WAKE#-PadB11)") (class "Default")
      (node (ref "Con1") (pin "B11") (pinfunction "WAKE#_B11") (pintype "passive"))
    )
    (net (code "88") (name "unconnected-(U18-6Y-Pad12)") (class "Default")
      (node (ref "U18") (pin "12") (pinfunction "6Y_12") (pintype "passive+no_connect"))
    )
    (net (code "89") (name "unconnected-(U24-Q-Pad3)") (class "Default")
      (node (ref "U24") (pin "3") (pinfunction "Q_3") (pintype "passive+no_connect"))
    )
  )
)
